# Qwiic_GPIO.net
KiCad netlist of a schematic drawn in EAGLE
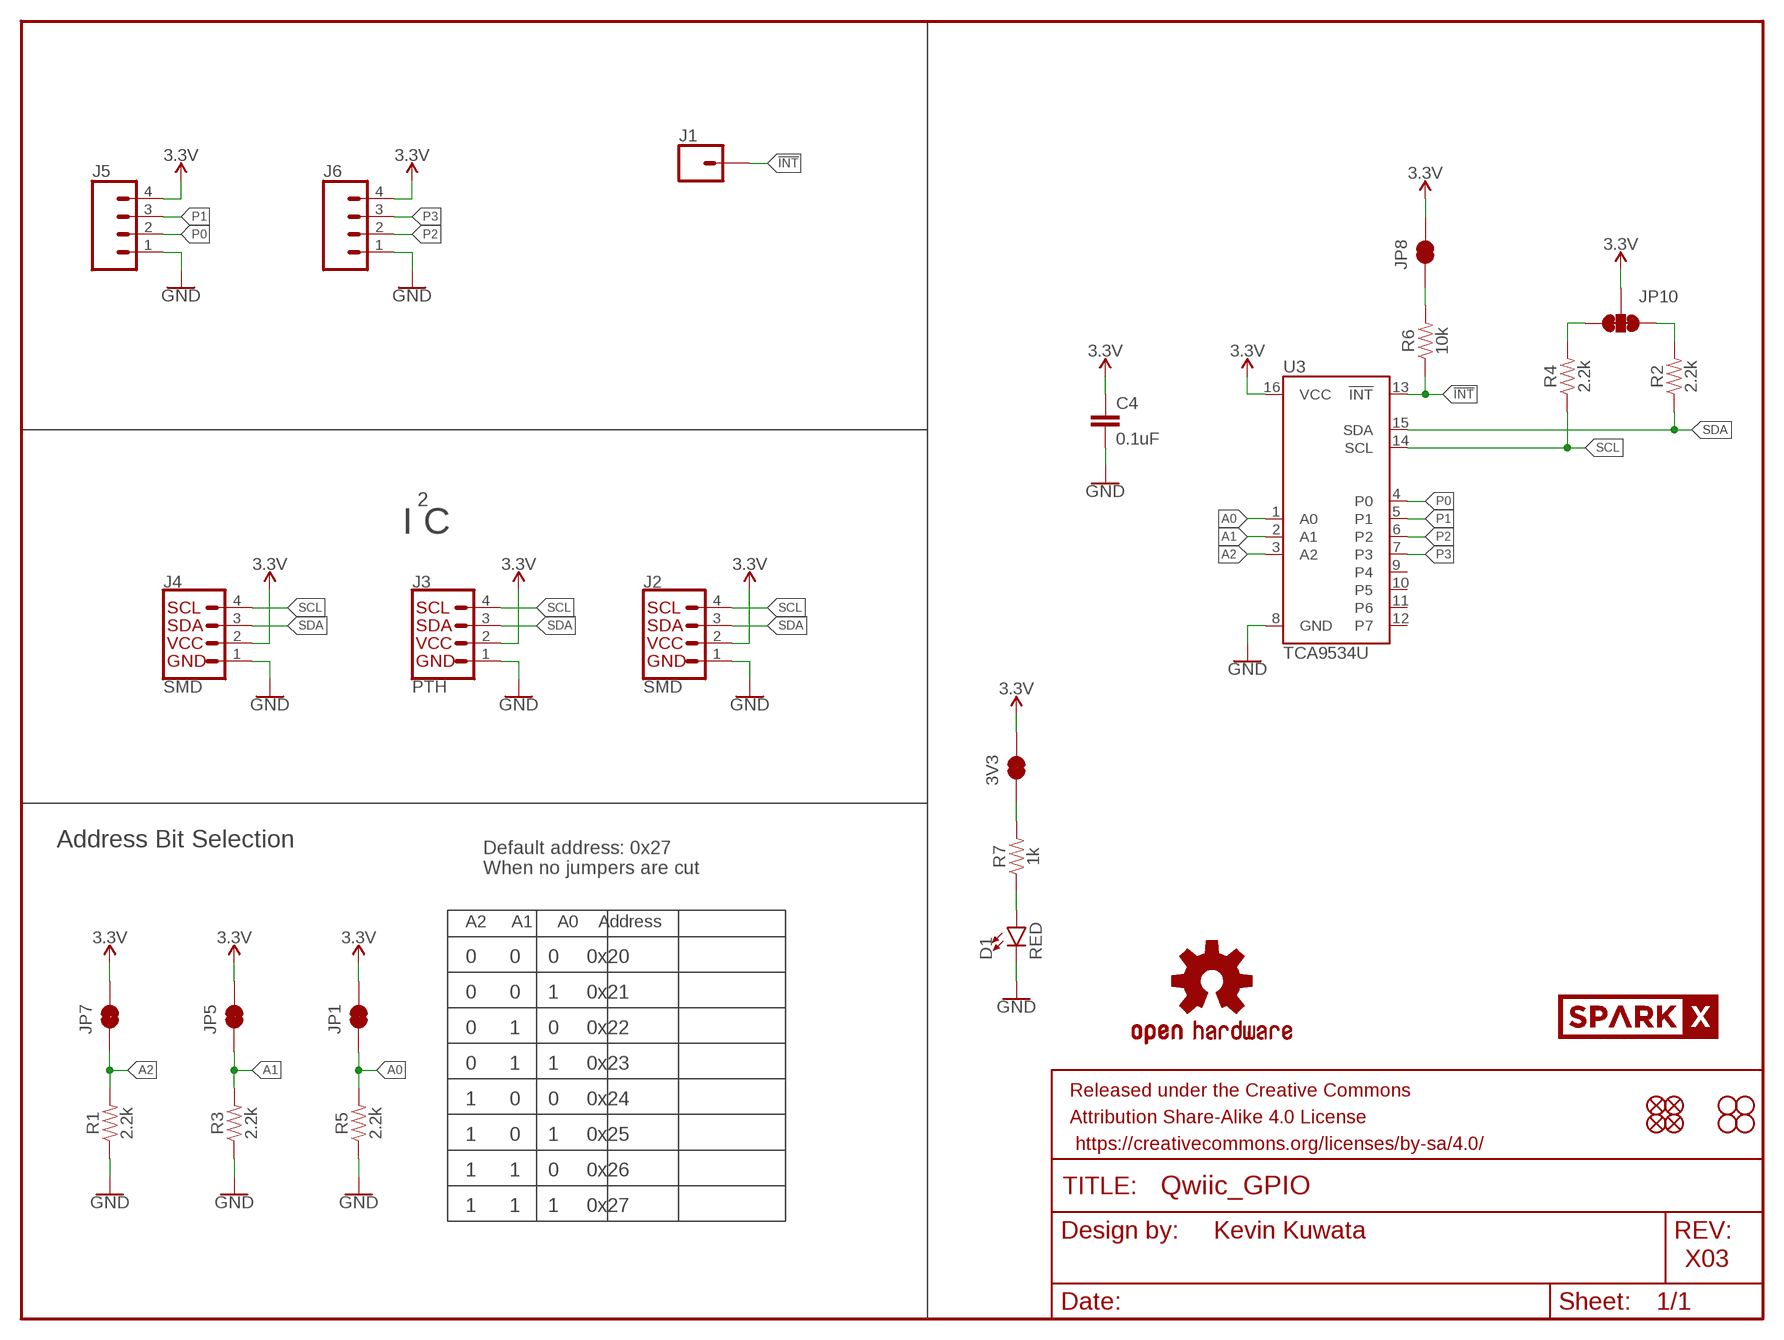
[diagram p0: schematic, sheet 1]

(export (version "E")
  (design (tool "Eeschema 10.0.6"))
  (components
    (comp (ref "3V3")
      (value "JUMPER-SMT_2_NC_TRACE_SILK")
      (footprint "eagle-import:SMT-JUMPER_2_NC_TRACE_SILK")
      (libsource (lib "eagle-import") (part "JUMPER-SMT_2_NC_TRACE_SILK"))
    )
    (comp (ref "C4")
      (value "0.1uF")
      (footprint "eagle-import:0603")
      (libsource (lib "eagle-import") (part "0.1UF-0603-25V-(+80/-20%)"))
    )
    (comp (ref "D1")
      (value "RED")
      (footprint "eagle-import:LED-0603")
      (libsource (lib "eagle-import") (part "LED-RED0603"))
    )
    (comp (ref "FD1")
      (value "FIDUCIAL1X2")
      (footprint "eagle-import:FIDUCIAL-1X2")
      (libsource (lib "eagle-import") (part "SparkFun-Aesthetics_FIDUCIAL1X2"))
    )
    (comp (ref "FD2")
      (value "FIDUCIAL1X2")
      (footprint "eagle-import:FIDUCIAL-1X2")
      (libsource (lib "eagle-import") (part "SparkFun-Aesthetics_FIDUCIAL1X2"))
    )
    (comp (ref "FRAME1")
      (value "FRAME-LETTER")
      (footprint "eagle-import:CREATIVE_COMMONS")
      (libsource (lib "eagle-import") (part "FRAME-LETTER"))
    )
    (comp (ref "H1")
      (value "STAND-OFF")
      (footprint "eagle-import:STAND-OFF")
      (libsource (lib "eagle-import") (part "SparkFun-Hardware_STAND-OFF"))
    )
    (comp (ref "H2")
      (value "STAND-OFF")
      (footprint "eagle-import:STAND-OFF")
      (libsource (lib "eagle-import") (part "SparkFun-Hardware_STAND-OFF"))
    )
    (comp (ref "J1")
      (value "CONN_01PTH_NO_SILK_YES_STOP")
      (footprint "eagle-import:1X01_NO_SILK")
      (libsource (lib "eagle-import") (part "CONN_01PTH_NO_SILK_YES_STOP"))
    )
    (comp (ref "J2")
      (value "SMD")
      (footprint "eagle-import:1X04_1MM_RA")
      (libsource (lib "eagle-import") (part "I2C_STANDARDJS-1MM"))
    )
    (comp (ref "J3")
      (value "PTH")
      (footprint "eagle-import:1X04_NO_SILK")
      (libsource (lib "eagle-import") (part "I2C_STANDARD_NO_SILK"))
    )
    (comp (ref "J4")
      (value "SMD")
      (footprint "eagle-import:1X04_1MM_RA")
      (libsource (lib "eagle-import") (part "I2C_STANDARDJS-1MM"))
    )
    (comp (ref "J5")
      (value "CONN_04LATCH")
      (footprint "eagle-import:LATCHTERMINAL-5MM-4")
      (fields (field (name "PROD_ID") "CON-14722"))
      (libsource (lib "eagle-import") (part "CONN_04LATCH"))
    )
    (comp (ref "J6")
      (value "CONN_04LATCH")
      (footprint "eagle-import:LATCHTERMINAL-5MM-4")
      (fields (field (name "PROD_ID") "CON-14722"))
      (libsource (lib "eagle-import") (part "CONN_04LATCH"))
    )
    (comp (ref "JP1")
      (value "JUMPER-SMT_2_NC_TRACE_SILK")
      (footprint "eagle-import:SMT-JUMPER_2_NC_TRACE_SILK")
      (libsource (lib "eagle-import") (part "JUMPER-SMT_2_NC_TRACE_SILK"))
    )
    (comp (ref "JP2")
      (value "FIDUCIAL1X2")
      (footprint "eagle-import:FIDUCIAL-1X2")
      (libsource (lib "eagle-import") (part "FIDUCIAL1X2"))
    )
    (comp (ref "JP3")
      (value "STAND-OFF")
      (footprint "eagle-import:STAND-OFF")
      (libsource (lib "eagle-import") (part "STAND-OFF"))
    )
    (comp (ref "JP4")
      (value "STAND-OFF")
      (footprint "eagle-import:STAND-OFF")
      (libsource (lib "eagle-import") (part "STAND-OFF"))
    )
    (comp (ref "JP5")
      (value "JUMPER-SMT_2_NC_TRACE_SILK")
      (footprint "eagle-import:SMT-JUMPER_2_NC_TRACE_SILK")
      (libsource (lib "eagle-import") (part "JUMPER-SMT_2_NC_TRACE_SILK"))
    )
    (comp (ref "JP6")
      (value "FIDUCIAL1X2")
      (footprint "eagle-import:FIDUCIAL-1X2")
      (libsource (lib "eagle-import") (part "FIDUCIAL1X2"))
    )
    (comp (ref "JP7")
      (value "JUMPER-SMT_2_NC_TRACE_SILK")
      (footprint "eagle-import:SMT-JUMPER_2_NC_TRACE_SILK")
      (libsource (lib "eagle-import") (part "JUMPER-SMT_2_NC_TRACE_SILK"))
    )
    (comp (ref "JP8")
      (value "JUMPER-SMT_2_NC_TRACE_SILK")
      (footprint "eagle-import:SMT-JUMPER_2_NC_TRACE_SILK")
      (libsource (lib "eagle-import") (part "JUMPER-SMT_2_NC_TRACE_SILK"))
    )
    (comp (ref "JP10")
      (value "JUMPER-SMT_3_2-NC_TRACE_SILK")
      (footprint "eagle-import:SMT-JUMPER_3_2-NC_TRACE_SILK")
      (libsource (lib "eagle-import") (part "JUMPER-SMT_3_2-NC_TRACE_SILK"))
    )
    (comp (ref "LOGO1")
      (value "OSHW-LOGOMINI")
      (footprint "eagle-import:OSHW-LOGO-MINI")
      (libsource (lib "eagle-import") (part "OSHW-LOGOMINI"))
    )
    (comp (ref "R1")
      (value "2.2k")
      (footprint "eagle-import:0603")
      (libsource (lib "eagle-import") (part "2.2KOHM-0603-1/10W-1%"))
    )
    (comp (ref "R2")
      (value "2.2k")
      (footprint "eagle-import:0603")
      (libsource (lib "eagle-import") (part "2.2KOHM-0603-1/10W-1%"))
    )
    (comp (ref "R3")
      (value "2.2k")
      (footprint "eagle-import:0603")
      (libsource (lib "eagle-import") (part "2.2KOHM-0603-1/10W-1%"))
    )
    (comp (ref "R4")
      (value "2.2k")
      (footprint "eagle-import:0603")
      (libsource (lib "eagle-import") (part "2.2KOHM-0603-1/10W-1%"))
    )
    (comp (ref "R5")
      (value "2.2k")
      (footprint "eagle-import:0603")
      (libsource (lib "eagle-import") (part "2.2KOHM-0603-1/10W-1%"))
    )
    (comp (ref "R6")
      (value "10k")
      (footprint "eagle-import:0603")
      (libsource (lib "eagle-import") (part "10KOHM-0603-1/10W-1%"))
    )
    (comp (ref "R7")
      (value "1k")
      (footprint "eagle-import:0603")
      (libsource (lib "eagle-import") (part "1KOHM-0603-1/10W-1%"))
    )
    (comp (ref "U$1")
      (value "SPARKX-LOGO3")
      (footprint "eagle-import:SPARKX-SMALL")
      (libsource (lib "eagle-import") (part "SPARKX-LOGO3"))
    )
    (comp (ref "U$2")
      (value "SPARKX-LOGO3")
      (footprint "eagle-import:SPARKX-SMALL")
      (libsource (lib "eagle-import") (part "SPARKX-LOGO3"))
    )
    (comp (ref "U3")
      (value "TCA9534U")
      (footprint "eagle-import:16SOIC")
      (libsource (lib "eagle-import") (part "TCA9534U"))
    )
  )
  (nets
    (net (code "1") (name "/~{INT}") (class "Default")
      (node (ref "J1") (pin "1") (pinfunction "1_1") (pintype "passive"))
      (node (ref "R6") (pin "1") (pinfunction "1_1") (pintype "passive"))
      (node (ref "U3") (pin "13") (pinfunction "~{INT}_13") (pintype "bidirectional"))
    )
    (net (code "2") (name "3.3V") (class "Default")
      (node (ref "3V3") (pin "2") (pinfunction "2_2") (pintype "passive"))
      (node (ref "C4") (pin "1") (pinfunction "1_1") (pintype "passive"))
      (node (ref "J2") (pin "2") (pinfunction "VCC_2") (pintype "power_in"))
      (node (ref "J3") (pin "2") (pinfunction "VCC_2") (pintype "power_in"))
      (node (ref "J4") (pin "2") (pinfunction "VCC_2") (pintype "power_in"))
      (node (ref "J5") (pin "4") (pinfunction "4_4") (pintype "passive"))
      (node (ref "J6") (pin "4") (pinfunction "4_4") (pintype "passive"))
      (node (ref "JP1") (pin "2") (pinfunction "2_2") (pintype "passive"))
      (node (ref "JP10") (pin "2") (pinfunction "2_2") (pintype "passive"))
      (node (ref "JP5") (pin "2") (pinfunction "2_2") (pintype "passive"))
      (node (ref "JP7") (pin "2") (pinfunction "2_2") (pintype "passive"))
      (node (ref "JP8") (pin "2") (pinfunction "2_2") (pintype "passive"))
      (node (ref "U3") (pin "16") (pinfunction "VCC_16") (pintype "bidirectional"))
    )
    (net (code "3") (name "A0") (class "Default")
      (node (ref "JP1") (pin "1") (pinfunction "1_1") (pintype "passive"))
      (node (ref "R5") (pin "2") (pinfunction "2_2") (pintype "passive"))
      (node (ref "U3") (pin "1") (pinfunction "A0_1") (pintype "bidirectional"))
    )
    (net (code "4") (name "A1") (class "Default")
      (node (ref "JP5") (pin "1") (pinfunction "1_1") (pintype "passive"))
      (node (ref "R3") (pin "2") (pinfunction "2_2") (pintype "passive"))
      (node (ref "U3") (pin "2") (pinfunction "A1_2") (pintype "bidirectional"))
    )
    (net (code "5") (name "A2") (class "Default")
      (node (ref "JP7") (pin "1") (pinfunction "1_1") (pintype "passive"))
      (node (ref "R1") (pin "2") (pinfunction "2_2") (pintype "passive"))
      (node (ref "U3") (pin "3") (pinfunction "A2_3") (pintype "bidirectional"))
    )
    (net (code "6") (name "GND") (class "Default")
      (node (ref "C4") (pin "2") (pinfunction "2_2") (pintype "passive"))
      (node (ref "D1") (pin "C") (pinfunction "C_C") (pintype "passive"))
      (node (ref "J2") (pin "1") (pinfunction "GND_1") (pintype "power_in"))
      (node (ref "J3") (pin "1") (pinfunction "GND_1") (pintype "power_in"))
      (node (ref "J4") (pin "1") (pinfunction "GND_1") (pintype "power_in"))
      (node (ref "J5") (pin "1") (pinfunction "1_1") (pintype "passive"))
      (node (ref "J6") (pin "1") (pinfunction "1_1") (pintype "passive"))
      (node (ref "R1") (pin "1") (pinfunction "1_1") (pintype "passive"))
      (node (ref "R3") (pin "1") (pinfunction "1_1") (pintype "passive"))
      (node (ref "R5") (pin "1") (pinfunction "1_1") (pintype "passive"))
      (node (ref "U3") (pin "8") (pinfunction "GND_8") (pintype "bidirectional"))
    )
    (net (code "7") (name "Net-(3V3-Pad1)") (class "Default")
      (node (ref "3V3") (pin "1") (pinfunction "1_1") (pintype "passive"))
      (node (ref "R7") (pin "2") (pinfunction "2_2") (pintype "passive"))
    )
    (net (code "8") (name "Net-(D1-PadA)") (class "Default")
      (node (ref "D1") (pin "A") (pinfunction "A_A") (pintype "passive"))
      (node (ref "R7") (pin "1") (pinfunction "1_1") (pintype "passive"))
    )
    (net (code "9") (name "Net-(JP8-Pad1)") (class "Default")
      (node (ref "JP8") (pin "1") (pinfunction "1_1") (pintype "passive"))
      (node (ref "R6") (pin "2") (pinfunction "2_2") (pintype "passive"))
    )
    (net (code "10") (name "Net-(JP10-Pad1)") (class "Default")
      (node (ref "JP10") (pin "1") (pinfunction "1_1") (pintype "passive"))
      (node (ref "R2") (pin "2") (pinfunction "2_2") (pintype "passive"))
    )
    (net (code "11") (name "Net-(JP10-Pad3)") (class "Default")
      (node (ref "JP10") (pin "3") (pinfunction "3_3") (pintype "passive"))
      (node (ref "R4") (pin "2") (pinfunction "2_2") (pintype "passive"))
    )
    (net (code "12") (name "P0") (class "Default")
      (node (ref "J5") (pin "2") (pinfunction "2_2") (pintype "passive"))
      (node (ref "U3") (pin "4") (pinfunction "P0_4") (pintype "bidirectional"))
    )
    (net (code "13") (name "P1") (class "Default")
      (node (ref "J5") (pin "3") (pinfunction "3_3") (pintype "passive"))
      (node (ref "U3") (pin "5") (pinfunction "P1_5") (pintype "bidirectional"))
    )
    (net (code "14") (name "P2") (class "Default")
      (node (ref "J6") (pin "2") (pinfunction "2_2") (pintype "passive"))
      (node (ref "U3") (pin "6") (pinfunction "P2_6") (pintype "bidirectional"))
    )
    (net (code "15") (name "P3") (class "Default")
      (node (ref "J6") (pin "3") (pinfunction "3_3") (pintype "passive"))
      (node (ref "U3") (pin "7") (pinfunction "P3_7") (pintype "bidirectional"))
    )
    (net (code "16") (name "SCL") (class "Default")
      (node (ref "J2") (pin "4") (pinfunction "SCL_4") (pintype "passive"))
      (node (ref "J3") (pin "4") (pinfunction "SCL_4") (pintype "passive"))
      (node (ref "J4") (pin "4") (pinfunction "SCL_4") (pintype "passive"))
      (node (ref "R4") (pin "1") (pinfunction "1_1") (pintype "passive"))
      (node (ref "U3") (pin "14") (pinfunction "SCL_14") (pintype "bidirectional"))
    )
    (net (code "17") (name "SDA") (class "Default")
      (node (ref "J2") (pin "3") (pinfunction "SDA_3") (pintype "passive"))
      (node (ref "J3") (pin "3") (pinfunction "SDA_3") (pintype "passive"))
      (node (ref "J4") (pin "3") (pinfunction "SDA_3") (pintype "passive"))
      (node (ref "R2") (pin "1") (pinfunction "1_1") (pintype "passive"))
      (node (ref "U3") (pin "15") (pinfunction "SDA_15") (pintype "bidirectional"))
    )
    (net (code "18") (name "unconnected-(U3-P4-Pad9)") (class "Default")
      (node (ref "U3") (pin "9") (pinfunction "P4_9") (pintype "bidirectional"))
    )
    (net (code "19") (name "unconnected-(U3-P5-Pad10)") (class "Default")
      (node (ref "U3") (pin "10") (pinfunction "P5_10") (pintype "bidirectional"))
    )
    (net (code "20") (name "unconnected-(U3-P6-Pad11)") (class "Default")
      (node (ref "U3") (pin "11") (pinfunction "P6_11") (pintype "bidirectional"))
    )
    (net (code "21") (name "unconnected-(U3-P7-Pad12)") (class "Default")
      (node (ref "U3") (pin "12") (pinfunction "P7_12") (pintype "bidirectional"))
    )
  )
)
